# FLUIDIC_CTRL.net
KiCad netlist of a schematic drawn in Altium Designer
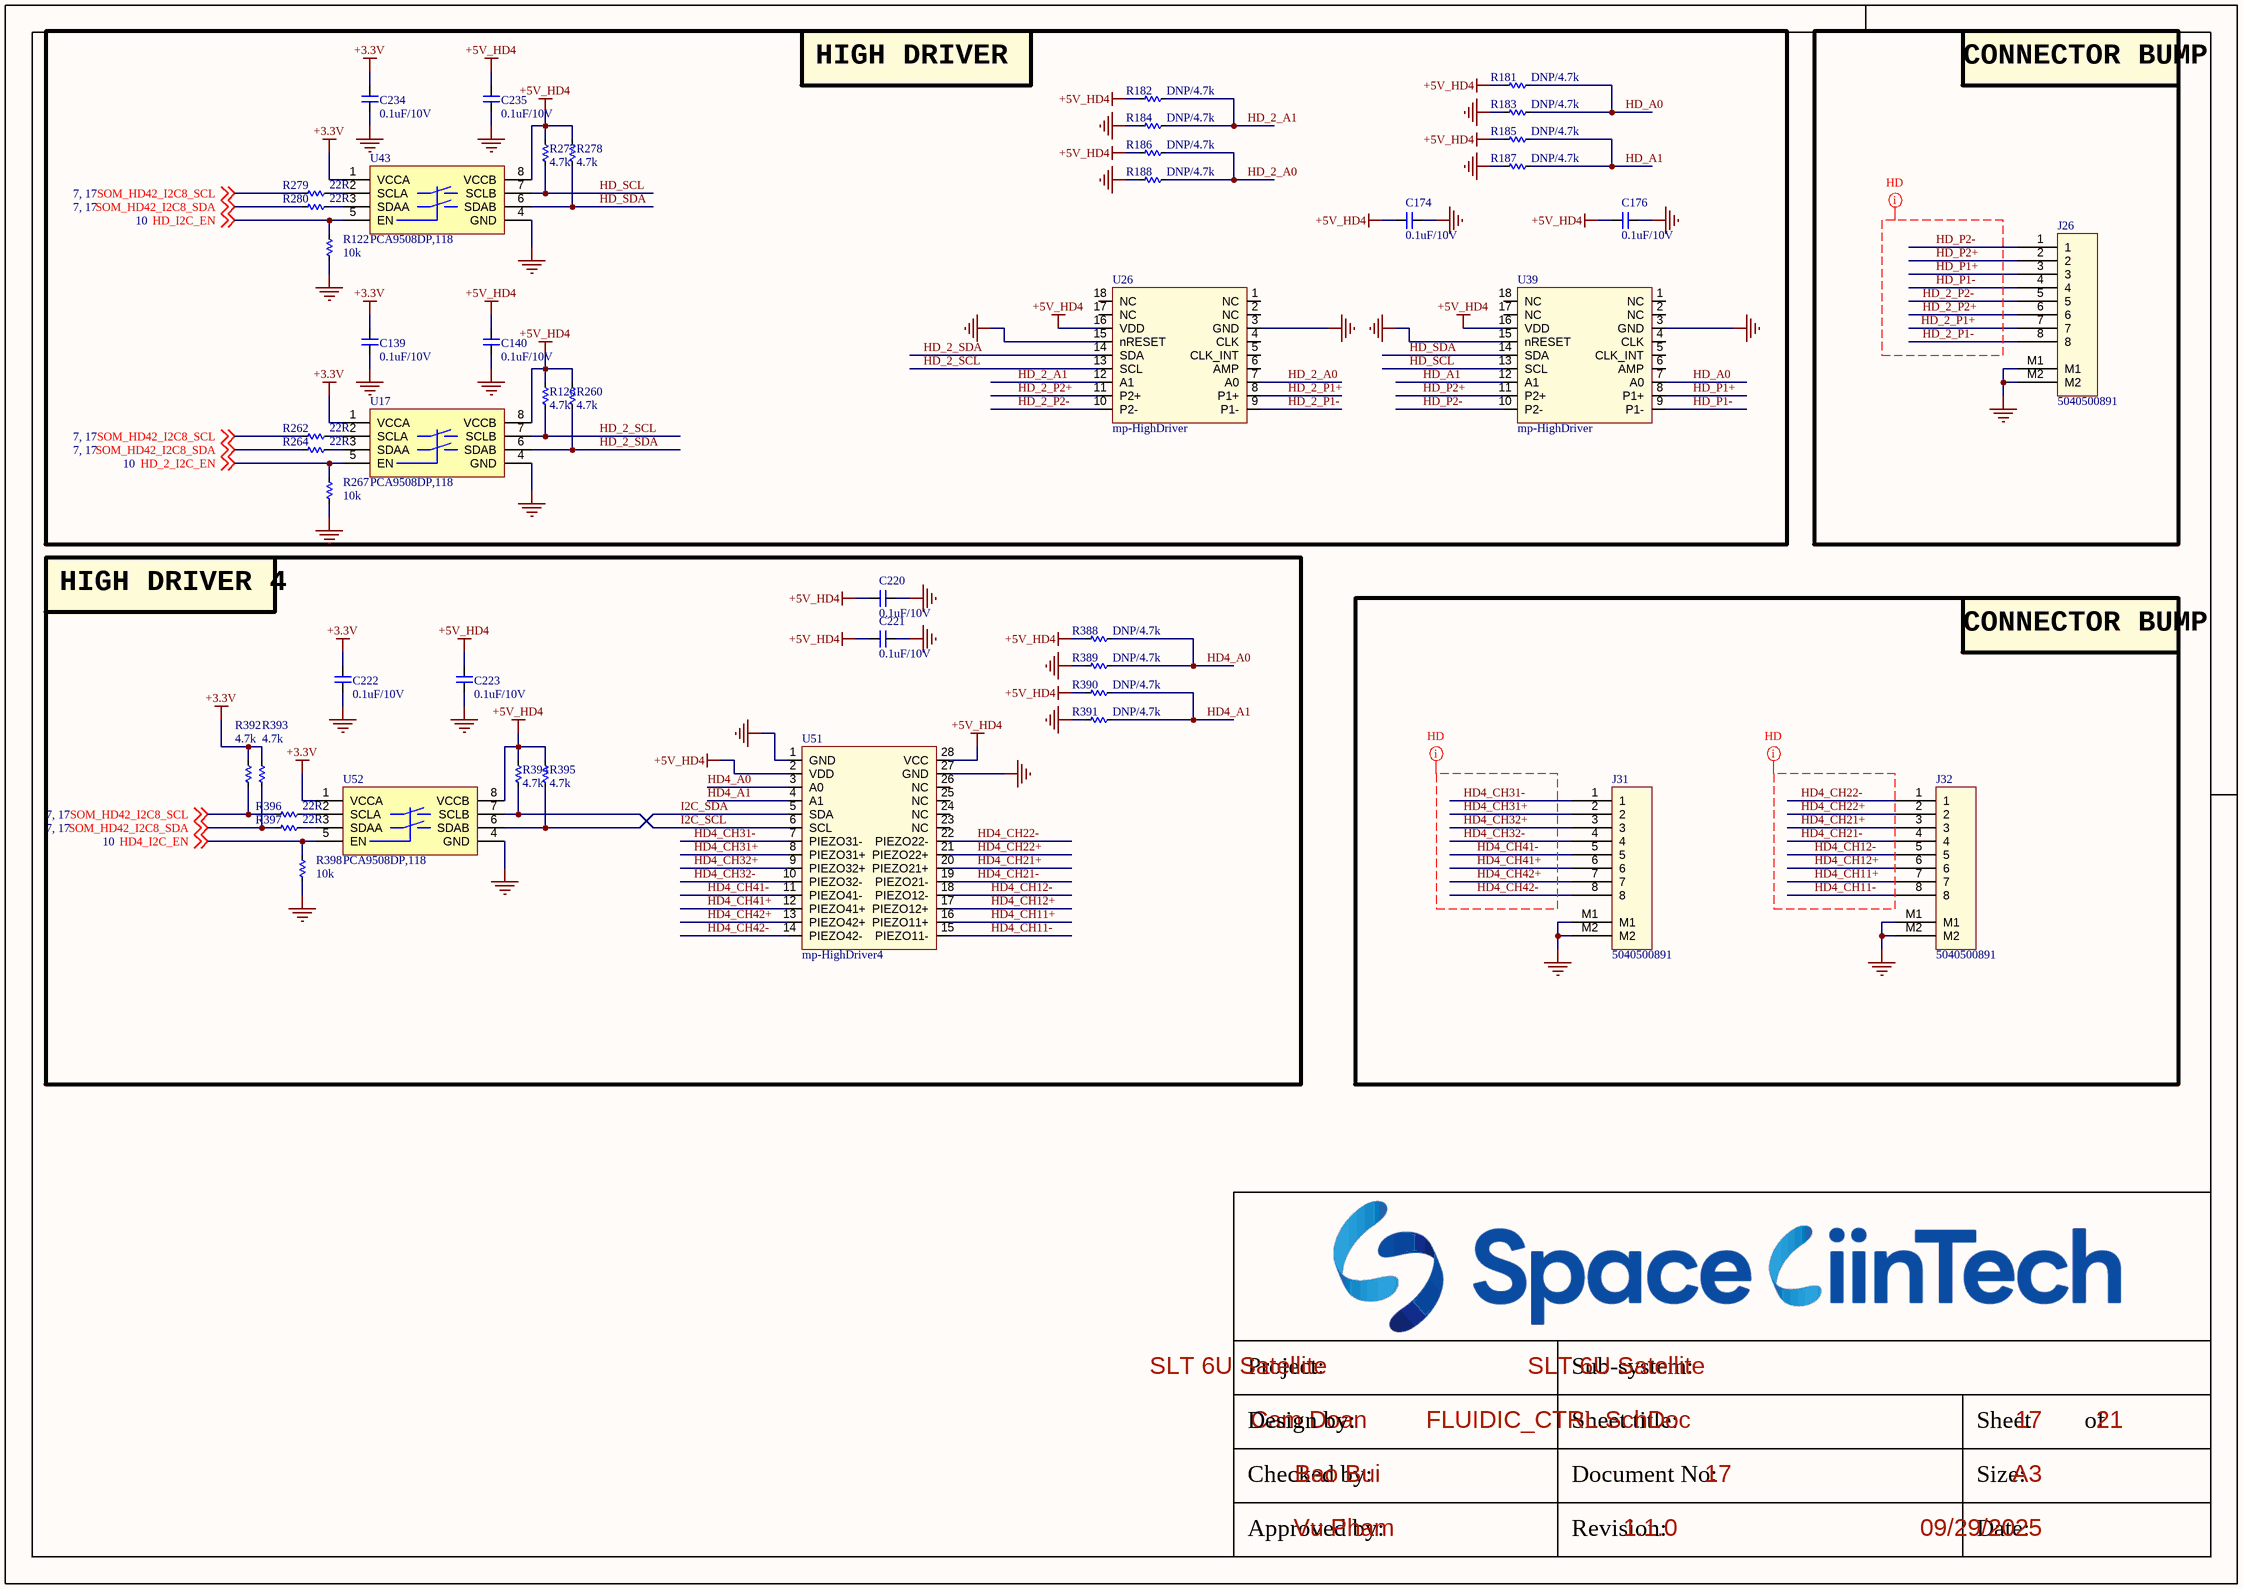
[diagram p0: FLUIDIC_CTRL.SchDoc]

(export (version "E")
  (design (tool "Eeschema 10.0.6"))
  (components
    (comp (ref "C139")
      (value "0.1uF/10V")
      (footprint "CAP_C_1005X60")
      (description "CAP CHIP")
      (libsource (lib "LABLIB") (part "_CAP_C_2"))
    )
    (comp (ref "C140")
      (value "0.1uF/10V")
      (footprint "CAP_C_1005X60")
      (description "CAP CHIP")
      (libsource (lib "LABLIB") (part "_CAP_C_2"))
    )
    (comp (ref "C174")
      (value "0.1uF/10V")
      (footprint "CAP_C_1005X60")
      (description "CAP CHIP")
      (libsource (lib "LABLIB") (part "_CAP_C_2"))
    )
    (comp (ref "C176")
      (value "0.1uF/10V")
      (footprint "CAP_C_1005X60")
      (description "CAP CHIP")
      (libsource (lib "LABLIB") (part "_CAP_C_2"))
    )
    (comp (ref "C220")
      (value "0.1uF/10V")
      (footprint "CAP_C_1005X60")
      (description "CAP CHIP")
      (libsource (lib "LABLIB") (part "_CAP_C_2"))
    )
    (comp (ref "C221")
      (value "0.1uF/10V")
      (footprint "CAP_C_1005X60")
      (description "CAP CHIP")
      (libsource (lib "LABLIB") (part "_CAP_C_2"))
    )
    (comp (ref "C222")
      (value "0.1uF/10V")
      (footprint "CAP_C_1005X60")
      (description "CAP CHIP")
      (libsource (lib "LABLIB") (part "_CAP_C_2"))
    )
    (comp (ref "C223")
      (value "0.1uF/10V")
      (footprint "CAP_C_1005X60")
      (description "CAP CHIP")
      (libsource (lib "LABLIB") (part "_CAP_C_2"))
    )
    (comp (ref "C234")
      (value "0.1uF/10V")
      (footprint "CAP_C_1005X60")
      (description "CAP CHIP")
      (libsource (lib "LABLIB") (part "_CAP_C_2"))
    )
    (comp (ref "C235")
      (value "0.1uF/10V")
      (footprint "CAP_C_1005X60")
      (description "CAP CHIP")
      (libsource (lib "LABLIB") (part "_CAP_C_2"))
    )
    (comp (ref "J26")
      (value "5040500891")
      (footprint "MOLEX_5040500891")
      (libsource (lib "LABLIB") (part "Header 8x1_2M"))
    )
    (comp (ref "J31")
      (value "5040500891")
      (footprint "MOLEX_5040500891")
      (libsource (lib "LABLIB") (part "Header 8x1_2M"))
    )
    (comp (ref "J32")
      (value "5040500891")
      (footprint "MOLEX_5040500891")
      (libsource (lib "LABLIB") (part "Header 8x1_2M"))
    )
    (comp (ref "R122")
      (value "10k")
      (footprint "RES_C_1005X40")
      (description "RES")
      (libsource (lib "LABLIB") (part "_RES_B_2"))
    )
    (comp (ref "R126")
      (value "4.7k")
      (footprint "RES_C_1005X40")
      (description "RES")
      (libsource (lib "LABLIB") (part "_RES_B_2"))
    )
    (comp (ref "R181")
      (value "DNP/4.7k")
      (footprint "RES_C_1005X40")
      (description "RES")
      (libsource (lib "LABLIB") (part "_RES_B_2"))
    )
    (comp (ref "R182")
      (value "DNP/4.7k")
      (footprint "RES_C_1005X40")
      (description "RES")
      (libsource (lib "LABLIB") (part "_RES_B_2"))
    )
    (comp (ref "R183")
      (value "DNP/4.7k")
      (footprint "RES_C_1005X40")
      (description "RES")
      (libsource (lib "LABLIB") (part "_RES_B_2"))
    )
    (comp (ref "R184")
      (value "DNP/4.7k")
      (footprint "RES_C_1005X40")
      (description "RES")
      (libsource (lib "LABLIB") (part "_RES_B_2"))
    )
    (comp (ref "R185")
      (value "DNP/4.7k")
      (footprint "RES_C_1005X40")
      (description "RES")
      (libsource (lib "LABLIB") (part "_RES_B_2"))
    )
    (comp (ref "R186")
      (value "DNP/4.7k")
      (footprint "RES_C_1005X40")
      (description "RES")
      (libsource (lib "LABLIB") (part "_RES_B_2"))
    )
    (comp (ref "R187")
      (value "DNP/4.7k")
      (footprint "RES_C_1005X40")
      (description "RES")
      (libsource (lib "LABLIB") (part "_RES_B_2"))
    )
    (comp (ref "R188")
      (value "DNP/4.7k")
      (footprint "RES_C_1005X40")
      (description "RES")
      (libsource (lib "LABLIB") (part "_RES_B_2"))
    )
    (comp (ref "R260")
      (value "4.7k")
      (footprint "RES_C_1005X40")
      (description "RES")
      (libsource (lib "LABLIB") (part "_RES_B_2"))
    )
    (comp (ref "R262")
      (value "22R")
      (footprint "RES_C_1005X40")
      (description "RES")
      (libsource (lib "LABLIB") (part "_RES_B_2"))
    )
    (comp (ref "R264")
      (value "22R")
      (footprint "RES_C_1005X40")
      (description "RES")
      (libsource (lib "LABLIB") (part "_RES_B_2"))
    )
    (comp (ref "R267")
      (value "10k")
      (footprint "RES_C_1005X40")
      (description "RES")
      (libsource (lib "LABLIB") (part "_RES_B_2"))
    )
    (comp (ref "R277")
      (value "4.7k")
      (footprint "RES_C_1005X40")
      (description "RES")
      (libsource (lib "LABLIB") (part "_RES_B_2"))
    )
    (comp (ref "R278")
      (value "4.7k")
      (footprint "RES_C_1005X40")
      (description "RES")
      (libsource (lib "LABLIB") (part "_RES_B_2"))
    )
    (comp (ref "R279")
      (value "22R")
      (footprint "RES_C_1005X40")
      (description "RES")
      (libsource (lib "LABLIB") (part "_RES_B_2"))
    )
    (comp (ref "R280")
      (value "22R")
      (footprint "RES_C_1005X40")
      (description "RES")
      (libsource (lib "LABLIB") (part "_RES_B_2"))
    )
    (comp (ref "R388")
      (value "DNP/4.7k")
      (footprint "RES_C_1005X40")
      (description "RES")
      (libsource (lib "LABLIB") (part "_RES_B_2"))
    )
    (comp (ref "R389")
      (value "DNP/4.7k")
      (footprint "RES_C_1005X40")
      (description "RES")
      (libsource (lib "LABLIB") (part "_RES_B_2"))
    )
    (comp (ref "R390")
      (value "DNP/4.7k")
      (footprint "RES_C_1005X40")
      (description "RES")
      (libsource (lib "LABLIB") (part "_RES_B_2"))
    )
    (comp (ref "R391")
      (value "DNP/4.7k")
      (footprint "RES_C_1005X40")
      (description "RES")
      (libsource (lib "LABLIB") (part "_RES_B_2"))
    )
    (comp (ref "R392")
      (value "4.7k")
      (footprint "RES_C_1005X40")
      (description "RES")
      (libsource (lib "LABLIB") (part "_RES_B_2"))
    )
    (comp (ref "R393")
      (value "4.7k")
      (footprint "RES_C_1005X40")
      (description "RES")
      (libsource (lib "LABLIB") (part "_RES_B_2"))
    )
    (comp (ref "R394")
      (value "4.7k")
      (footprint "RES_C_1005X40")
      (description "RES")
      (libsource (lib "LABLIB") (part "_RES_B_2"))
    )
    (comp (ref "R395")
      (value "4.7k")
      (footprint "RES_C_1005X40")
      (description "RES")
      (libsource (lib "LABLIB") (part "_RES_B_2"))
    )
    (comp (ref "R396")
      (value "22R")
      (footprint "RES_C_1005X40")
      (description "RES")
      (libsource (lib "LABLIB") (part "_RES_B_2"))
    )
    (comp (ref "R397")
      (value "22R")
      (footprint "RES_C_1005X40")
      (description "RES")
      (libsource (lib "LABLIB") (part "_RES_B_2"))
    )
    (comp (ref "R398")
      (value "10k")
      (footprint "RES_C_1005X40")
      (description "RES")
      (libsource (lib "LABLIB") (part "_RES_B_2"))
    )
    (comp (ref "U17")
      (value "PCA9508DP,118")
      (footprint "TSOP8")
      (libsource (lib "EXP_HW_V3") (part "PCA9508DP,118"))
    )
    (comp (ref "U26")
      (value "mp-HighDriver")
      (footprint "MP_HIGHDRIVER")
      (libsource (lib "new_component") (part "mp-HighDriver"))
    )
    (comp (ref "U39")
      (value "mp-HighDriver")
      (footprint "MP_HIGHDRIVER")
      (libsource (lib "new_component") (part "mp-HighDriver"))
    )
    (comp (ref "U43")
      (value "PCA9508DP,118")
      (footprint "TSOP8")
      (libsource (lib "EXP_HW_V3") (part "PCA9508DP,118"))
    )
    (comp (ref "U51")
      (value "mp-HighDriver4")
      (footprint "MP_HIGHDRIVER4")
      (libsource (lib "new_component") (part "mp_HighDriver4"))
    )
    (comp (ref "U52")
      (value "PCA9508DP,118")
      (footprint "TSOP8")
      (libsource (lib "EXP_HW_V3") (part "PCA9508DP,118"))
    )
  )
  (nets
    (net (code "1") (name "+3.3V") (class "Default")
      (node (ref "C139") (pin "2") (pinfunction "2_2") (pintype "passive"))
      (node (ref "C222") (pin "2") (pinfunction "2_2") (pintype "passive"))
      (node (ref "C234") (pin "2") (pinfunction "2_2") (pintype "passive"))
      (node (ref "R392") (pin "1") (pinfunction "1_1") (pintype "passive"))
      (node (ref "R393") (pin "1") (pinfunction "1_1") (pintype "passive"))
      (node (ref "U17") (pin "1") (pinfunction "VCCA_1") (pintype "passive"))
      (node (ref "U43") (pin "1") (pinfunction "VCCA_1") (pintype "passive"))
      (node (ref "U52") (pin "1") (pinfunction "VCCA_1") (pintype "passive"))
    )
    (net (code "2") (name "+5V_HD4") (class "Default")
      (node (ref "C140") (pin "2") (pinfunction "2_2") (pintype "passive"))
      (node (ref "C174") (pin "2") (pinfunction "2_2") (pintype "passive"))
      (node (ref "C176") (pin "2") (pinfunction "2_2") (pintype "passive"))
      (node (ref "C220") (pin "2") (pinfunction "2_2") (pintype "passive"))
      (node (ref "C221") (pin "2") (pinfunction "2_2") (pintype "passive"))
      (node (ref "C223") (pin "2") (pinfunction "2_2") (pintype "passive"))
      (node (ref "C235") (pin "2") (pinfunction "2_2") (pintype "passive"))
      (node (ref "R126") (pin "1") (pinfunction "1_1") (pintype "passive"))
      (node (ref "R181") (pin "1") (pinfunction "1_1") (pintype "passive"))
      (node (ref "R182") (pin "1") (pinfunction "1_1") (pintype "passive"))
      (node (ref "R185") (pin "1") (pinfunction "1_1") (pintype "passive"))
      (node (ref "R186") (pin "1") (pinfunction "1_1") (pintype "passive"))
      (node (ref "R260") (pin "1") (pinfunction "1_1") (pintype "passive"))
      (node (ref "R277") (pin "1") (pinfunction "1_1") (pintype "passive"))
      (node (ref "R278") (pin "1") (pinfunction "1_1") (pintype "passive"))
      (node (ref "R388") (pin "1") (pinfunction "1_1") (pintype "passive"))
      (node (ref "R390") (pin "1") (pinfunction "1_1") (pintype "passive"))
      (node (ref "R394") (pin "1") (pinfunction "1_1") (pintype "passive"))
      (node (ref "R395") (pin "1") (pinfunction "1_1") (pintype "passive"))
      (node (ref "U17") (pin "8") (pinfunction "VCCB_8") (pintype "passive"))
      (node (ref "U26") (pin "16") (pinfunction "VDD_16") (pintype "power_in"))
      (node (ref "U39") (pin "16") (pinfunction "VDD_16") (pintype "power_in"))
      (node (ref "U43") (pin "8") (pinfunction "VCCB_8") (pintype "passive"))
      (node (ref "U51") (pin "2") (pinfunction "VDD_2") (pintype "power_in"))
      (node (ref "U51") (pin "28") (pinfunction "VCC_28") (pintype "power_in"))
      (node (ref "U52") (pin "8") (pinfunction "VCCB_8") (pintype "passive"))
    )
    (net (code "3") (name "/HD4_A0") (class "Default")
      (node (ref "R388") (pin "2") (pinfunction "2_2") (pintype "passive"))
      (node (ref "R389") (pin "2") (pinfunction "2_2") (pintype "passive"))
      (node (ref "U51") (pin "3") (pinfunction "A0_3") (pintype "passive"))
    )
    (net (code "4") (name "/HD4_A1") (class "Default")
      (node (ref "R390") (pin "2") (pinfunction "2_2") (pintype "passive"))
      (node (ref "R391") (pin "2") (pinfunction "2_2") (pintype "passive"))
      (node (ref "U51") (pin "4") (pinfunction "A1_4") (pintype "passive"))
    )
    (net (code "5") (name "/HD4_CH11+") (class "Default")
      (node (ref "J32") (pin "7") (pinfunction "7_7") (pintype "passive"))
      (node (ref "U51") (pin "16") (pinfunction "PIEZO11+_16") (pintype "passive"))
    )
    (net (code "6") (name "/HD4_CH11-") (class "Default")
      (node (ref "J32") (pin "8") (pinfunction "8_8") (pintype "passive"))
      (node (ref "U51") (pin "15") (pinfunction "PIEZO11-_15") (pintype "passive"))
    )
    (net (code "7") (name "/HD4_CH12+") (class "Default")
      (node (ref "J32") (pin "6") (pinfunction "6_6") (pintype "passive"))
      (node (ref "U51") (pin "17") (pinfunction "PIEZO12+_17") (pintype "passive"))
    )
    (net (code "8") (name "/HD4_CH12-") (class "Default")
      (node (ref "J32") (pin "5") (pinfunction "5_5") (pintype "passive"))
      (node (ref "U51") (pin "18") (pinfunction "PIEZO12-_18") (pintype "passive"))
    )
    (net (code "9") (name "/HD4_CH21+") (class "Default")
      (node (ref "J32") (pin "3") (pinfunction "3_3") (pintype "passive"))
      (node (ref "U51") (pin "20") (pinfunction "PIEZO21+_20") (pintype "passive"))
    )
    (net (code "10") (name "/HD4_CH21-") (class "Default")
      (node (ref "J32") (pin "4") (pinfunction "4_4") (pintype "passive"))
      (node (ref "U51") (pin "19") (pinfunction "PIEZO21-_19") (pintype "passive"))
    )
    (net (code "11") (name "/HD4_CH22+") (class "Default")
      (node (ref "J32") (pin "2") (pinfunction "2_2") (pintype "passive"))
      (node (ref "U51") (pin "21") (pinfunction "PIEZO22+_21") (pintype "passive"))
    )
    (net (code "12") (name "/HD4_CH22-") (class "Default")
      (node (ref "J32") (pin "1") (pinfunction "1_1") (pintype "passive"))
      (node (ref "U51") (pin "22") (pinfunction "PIEZO22-_22") (pintype "passive"))
    )
    (net (code "13") (name "/HD4_CH31+") (class "Default")
      (node (ref "J31") (pin "2") (pinfunction "2_2") (pintype "passive"))
      (node (ref "U51") (pin "8") (pinfunction "PIEZO31+_8") (pintype "passive"))
    )
    (net (code "14") (name "/HD4_CH31-") (class "Default")
      (node (ref "J31") (pin "1") (pinfunction "1_1") (pintype "passive"))
      (node (ref "U51") (pin "7") (pinfunction "PIEZO31-_7") (pintype "passive"))
    )
    (net (code "15") (name "/HD4_CH32+") (class "Default")
      (node (ref "J31") (pin "3") (pinfunction "3_3") (pintype "passive"))
      (node (ref "U51") (pin "9") (pinfunction "PIEZO32+_9") (pintype "passive"))
    )
    (net (code "16") (name "/HD4_CH32-") (class "Default")
      (node (ref "J31") (pin "4") (pinfunction "4_4") (pintype "passive"))
      (node (ref "U51") (pin "10") (pinfunction "PIEZO32-_10") (pintype "passive"))
    )
    (net (code "17") (name "/HD4_CH41+") (class "Default")
      (node (ref "J31") (pin "6") (pinfunction "6_6") (pintype "passive"))
      (node (ref "U51") (pin "12") (pinfunction "PIEZO41+_12") (pintype "passive"))
    )
    (net (code "18") (name "/HD4_CH41-") (class "Default")
      (node (ref "J31") (pin "5") (pinfunction "5_5") (pintype "passive"))
      (node (ref "U51") (pin "11") (pinfunction "PIEZO41-_11") (pintype "passive"))
    )
    (net (code "19") (name "/HD4_CH42+") (class "Default")
      (node (ref "J31") (pin "7") (pinfunction "7_7") (pintype "passive"))
      (node (ref "U51") (pin "13") (pinfunction "PIEZO42+_13") (pintype "passive"))
    )
    (net (code "20") (name "/HD4_CH42-") (class "Default")
      (node (ref "J31") (pin "8") (pinfunction "8_8") (pintype "passive"))
      (node (ref "U51") (pin "14") (pinfunction "PIEZO42-_14") (pintype "passive"))
    )
    (net (code "21") (name "/HD_2_A0") (class "Default")
      (node (ref "R186") (pin "2") (pinfunction "2_2") (pintype "passive"))
      (node (ref "R188") (pin "2") (pinfunction "2_2") (pintype "passive"))
      (node (ref "U26") (pin "7") (pinfunction "A0_7") (pintype "passive"))
    )
    (net (code "22") (name "/HD_2_A1") (class "Default")
      (node (ref "R182") (pin "2") (pinfunction "2_2") (pintype "passive"))
      (node (ref "R184") (pin "2") (pinfunction "2_2") (pintype "passive"))
      (node (ref "U26") (pin "12") (pinfunction "A1_12") (pintype "passive"))
    )
    (net (code "23") (name "/HD_2_P1+") (class "Default")
      (node (ref "J26") (pin "7") (pinfunction "7_7") (pintype "passive"))
      (node (ref "U26") (pin "8") (pinfunction "P1+_8") (pintype "passive"))
    )
    (net (code "24") (name "/HD_2_P1-") (class "Default")
      (node (ref "J26") (pin "8") (pinfunction "8_8") (pintype "passive"))
      (node (ref "U26") (pin "9") (pinfunction "P1-_9") (pintype "passive"))
    )
    (net (code "25") (name "/HD_2_P2+") (class "Default")
      (node (ref "J26") (pin "6") (pinfunction "6_6") (pintype "passive"))
      (node (ref "U26") (pin "11") (pinfunction "P2+_11") (pintype "passive"))
    )
    (net (code "26") (name "/HD_2_P2-") (class "Default")
      (node (ref "J26") (pin "5") (pinfunction "5_5") (pintype "passive"))
      (node (ref "U26") (pin "10") (pinfunction "P2-_10") (pintype "passive"))
    )
    (net (code "27") (name "/HD_2_SCL") (class "Default")
      (node (ref "R126") (pin "2") (pinfunction "2_2") (pintype "passive"))
      (node (ref "U17") (pin "7") (pinfunction "SCLB_7") (pintype "passive"))
      (node (ref "U26") (pin "13") (pinfunction "SCL_13") (pintype "passive"))
    )
    (net (code "28") (name "/HD_2_SDA") (class "Default")
      (node (ref "R260") (pin "2") (pinfunction "2_2") (pintype "passive"))
      (node (ref "U17") (pin "6") (pinfunction "SDAB_6") (pintype "passive"))
      (node (ref "U26") (pin "14") (pinfunction "SDA_14") (pintype "passive"))
    )
    (net (code "29") (name "/HD_A0") (class "Default")
      (node (ref "R181") (pin "2") (pinfunction "2_2") (pintype "passive"))
      (node (ref "R183") (pin "2") (pinfunction "2_2") (pintype "passive"))
      (node (ref "U39") (pin "7") (pinfunction "A0_7") (pintype "passive"))
    )
    (net (code "30") (name "/HD_A1") (class "Default")
      (node (ref "R185") (pin "2") (pinfunction "2_2") (pintype "passive"))
      (node (ref "R187") (pin "2") (pinfunction "2_2") (pintype "passive"))
      (node (ref "U39") (pin "12") (pinfunction "A1_12") (pintype "passive"))
    )
    (net (code "31") (name "/HD_P1+") (class "Default")
      (node (ref "J26") (pin "3") (pinfunction "3_3") (pintype "passive"))
      (node (ref "U39") (pin "8") (pinfunction "P1+_8") (pintype "passive"))
    )
    (net (code "32") (name "/HD_P1-") (class "Default")
      (node (ref "J26") (pin "4") (pinfunction "4_4") (pintype "passive"))
      (node (ref "U39") (pin "9") (pinfunction "P1-_9") (pintype "passive"))
    )
    (net (code "33") (name "/HD_P2+") (class "Default")
      (node (ref "J26") (pin "2") (pinfunction "2_2") (pintype "passive"))
      (node (ref "U39") (pin "11") (pinfunction "P2+_11") (pintype "passive"))
    )
    (net (code "34") (name "/HD_P2-") (class "Default")
      (node (ref "J26") (pin "1") (pinfunction "1_1") (pintype "passive"))
      (node (ref "U39") (pin "10") (pinfunction "P2-_10") (pintype "passive"))
    )
    (net (code "35") (name "/HD_SCL") (class "Default")
      (node (ref "R277") (pin "2") (pinfunction "2_2") (pintype "passive"))
      (node (ref "U39") (pin "13") (pinfunction "SCL_13") (pintype "passive"))
      (node (ref "U43") (pin "7") (pinfunction "SCLB_7") (pintype "passive"))
    )
    (net (code "36") (name "/HD_SDA") (class "Default")
      (node (ref "R278") (pin "2") (pinfunction "2_2") (pintype "passive"))
      (node (ref "U39") (pin "14") (pinfunction "SDA_14") (pintype "passive"))
      (node (ref "U43") (pin "6") (pinfunction "SDAB_6") (pintype "passive"))
    )
    (net (code "37") (name "/I2C_SCL") (class "Default")
      (node (ref "R394") (pin "2") (pinfunction "2_2") (pintype "passive"))
      (node (ref "U51") (pin "6") (pinfunction "SCL_6") (pintype "passive"))
      (node (ref "U52") (pin "7") (pinfunction "SCLB_7") (pintype "passive"))
    )
    (net (code "38") (name "/I2C_SDA") (class "Default")
      (node (ref "R395") (pin "2") (pinfunction "2_2") (pintype "passive"))
      (node (ref "U51") (pin "5") (pinfunction "SDA_5") (pintype "passive"))
      (node (ref "U52") (pin "6") (pinfunction "SDAB_6") (pintype "passive"))
    )
    (net (code "39") (name "GND") (class "Default")
      (node (ref "C139") (pin "1") (pinfunction "1_1") (pintype "passive"))
      (node (ref "C140") (pin "1") (pinfunction "1_1") (pintype "passive"))
      (node (ref "C174") (pin "1") (pinfunction "1_1") (pintype "passive"))
      (node (ref "C176") (pin "1") (pinfunction "1_1") (pintype "passive"))
      (node (ref "C220") (pin "1") (pinfunction "1_1") (pintype "passive"))
      (node (ref "C221") (pin "1") (pinfunction "1_1") (pintype "passive"))
      (node (ref "C222") (pin "1") (pinfunction "1_1") (pintype "passive"))
      (node (ref "C223") (pin "1") (pinfunction "1_1") (pintype "passive"))
      (node (ref "C234") (pin "1") (pinfunction "1_1") (pintype "passive"))
      (node (ref "C235") (pin "1") (pinfunction "1_1") (pintype "passive"))
      (node (ref "J26") (pin "M1") (pinfunction "M1_M1") (pintype "passive"))
      (node (ref "J26") (pin "M2") (pinfunction "M2_M2") (pintype "passive"))
      (node (ref "J31") (pin "M1") (pinfunction "M1_M1") (pintype "passive"))
      (node (ref "J31") (pin "M2") (pinfunction "M2_M2") (pintype "passive"))
      (node (ref "J32") (pin "M1") (pinfunction "M1_M1") (pintype "passive"))
      (node (ref "J32") (pin "M2") (pinfunction "M2_M2") (pintype "passive"))
      (node (ref "R122") (pin "2") (pinfunction "2_2") (pintype "passive"))
      (node (ref "R183") (pin "1") (pinfunction "1_1") (pintype "passive"))
      (node (ref "R184") (pin "1") (pinfunction "1_1") (pintype "passive"))
      (node (ref "R187") (pin "1") (pinfunction "1_1") (pintype "passive"))
      (node (ref "R188") (pin "1") (pinfunction "1_1") (pintype "passive"))
      (node (ref "R267") (pin "2") (pinfunction "2_2") (pintype "passive"))
      (node (ref "R389") (pin "1") (pinfunction "1_1") (pintype "passive"))
      (node (ref "R391") (pin "1") (pinfunction "1_1") (pintype "passive"))
      (node (ref "R398") (pin "2") (pinfunction "2_2") (pintype "passive"))
      (node (ref "U17") (pin "4") (pinfunction "GND_4") (pintype "passive"))
      (node (ref "U26") (pin "15") (pinfunction "nRESET_15") (pintype "passive"))
      (node (ref "U26") (pin "3") (pinfunction "GND_3") (pintype "power_in"))
      (node (ref "U39") (pin "15") (pinfunction "nRESET_15") (pintype "passive"))
      (node (ref "U39") (pin "3") (pinfunction "GND_3") (pintype "power_in"))
      (node (ref "U43") (pin "4") (pinfunction "GND_4") (pintype "passive"))
      (node (ref "U51") (pin "1") (pinfunction "GND_1") (pintype "power_in"))
      (node (ref "U51") (pin "27") (pinfunction "GND_27") (pintype "power_in"))
      (node (ref "U52") (pin "4") (pinfunction "GND_4") (pintype "passive"))
    )
    (net (code "40") (name "HD4_I2C_EN") (class "Default")
      (node (ref "R398") (pin "1") (pinfunction "1_1") (pintype "passive"))
      (node (ref "U52") (pin "5") (pinfunction "EN_5") (pintype "passive"))
    )
    (net (code "41") (name "HD_2_I2C_EN") (class "Default")
      (node (ref "R267") (pin "1") (pinfunction "1_1") (pintype "passive"))
      (node (ref "U17") (pin "5") (pinfunction "EN_5") (pintype "passive"))
    )
    (net (code "42") (name "HD_I2C_EN") (class "Default")
      (node (ref "R122") (pin "1") (pinfunction "1_1") (pintype "passive"))
      (node (ref "U43") (pin "5") (pinfunction "EN_5") (pintype "passive"))
    )
    (net (code "43") (name "Net-(U17-SCLA)") (class "Default")
      (node (ref "R262") (pin "1") (pinfunction "1_1") (pintype "passive"))
      (node (ref "U17") (pin "2") (pinfunction "SCLA_2") (pintype "passive"))
    )
    (net (code "44") (name "Net-(U17-SDAA)") (class "Default")
      (node (ref "R264") (pin "1") (pinfunction "1_1") (pintype "passive"))
      (node (ref "U17") (pin "3") (pinfunction "SDAA_3") (pintype "passive"))
    )
    (net (code "45") (name "Net-(U43-SCLA)") (class "Default")
      (node (ref "R279") (pin "1") (pinfunction "1_1") (pintype "passive"))
      (node (ref "U43") (pin "2") (pinfunction "SCLA_2") (pintype "passive"))
    )
    (net (code "46") (name "Net-(U43-SDAA)") (class "Default")
      (node (ref "R280") (pin "1") (pinfunction "1_1") (pintype "passive"))
      (node (ref "U43") (pin "3") (pinfunction "SDAA_3") (pintype "passive"))
    )
    (net (code "47") (name "Net-(U52-SCLA)") (class "Default")
      (node (ref "R396") (pin "1") (pinfunction "1_1") (pintype "passive"))
      (node (ref "U52") (pin "2") (pinfunction "SCLA_2") (pintype "passive"))
    )
    (net (code "48") (name "Net-(U52-SDAA)") (class "Default")
      (node (ref "R397") (pin "1") (pinfunction "1_1") (pintype "passive"))
      (node (ref "U52") (pin "3") (pinfunction "SDAA_3") (pintype "passive"))
    )
    (net (code "49") (name "SOM_HD42_I2C8_SCL") (class "Default")
      (node (ref "R262") (pin "2") (pinfunction "2_2") (pintype "passive"))
      (node (ref "R279") (pin "2") (pinfunction "2_2") (pintype "passive"))
      (node (ref "R392") (pin "2") (pinfunction "2_2") (pintype "passive"))
      (node (ref "R396") (pin "2") (pinfunction "2_2") (pintype "passive"))
    )
    (net (code "50") (name "SOM_HD42_I2C8_SDA") (class "Default")
      (node (ref "R264") (pin "2") (pinfunction "2_2") (pintype "passive"))
      (node (ref "R280") (pin "2") (pinfunction "2_2") (pintype "passive"))
      (node (ref "R393") (pin "2") (pinfunction "2_2") (pintype "passive"))
      (node (ref "R397") (pin "2") (pinfunction "2_2") (pintype "passive"))
    )
    (net (code "51") (name "unconnected-(U26-AMP-Pad6)") (class "Default")
      (node (ref "U26") (pin "6") (pinfunction "AMP_6") (pintype "passive"))
    )
    (net (code "52") (name "unconnected-(U26-CLK-Pad4)") (class "Default")
      (node (ref "U26") (pin "4") (pinfunction "CLK_4") (pintype "passive"))
    )
    (net (code "53") (name "unconnected-(U26-CLK_INT-Pad5)") (class "Default")
      (node (ref "U26") (pin "5") (pinfunction "CLK_INT_5") (pintype "passive"))
    )
    (net (code "54") (name "unconnected-(U26-NC-Pad1)") (class "Default")
      (node (ref "U26") (pin "1") (pinfunction "NC_1") (pintype "passive"))
    )
    (net (code "55") (name "unconnected-(U26-NC-Pad2)") (class "Default")
      (node (ref "U26") (pin "2") (pinfunction "NC_2") (pintype "passive"))
    )
    (net (code "56") (name "unconnected-(U26-NC-Pad17)") (class "Default")
      (node (ref "U26") (pin "17") (pinfunction "NC_17") (pintype "passive"))
    )
    (net (code "57") (name "unconnected-(U26-NC-Pad18)") (class "Default")
      (node (ref "U26") (pin "18") (pinfunction "NC_18") (pintype "passive"))
    )
    (net (code "58") (name "unconnected-(U39-AMP-Pad6)") (class "Default")
      (node (ref "U39") (pin "6") (pinfunction "AMP_6") (pintype "passive"))
    )
    (net (code "59") (name "unconnected-(U39-CLK-Pad4)") (class "Default")
      (node (ref "U39") (pin "4") (pinfunction "CLK_4") (pintype "passive"))
    )
    (net (code "60") (name "unconnected-(U39-CLK_INT-Pad5)") (class "Default")
      (node (ref "U39") (pin "5") (pinfunction "CLK_INT_5") (pintype "passive"))
    )
    (net (code "61") (name "unconnected-(U39-NC-Pad1)") (class "Default")
      (node (ref "U39") (pin "1") (pinfunction "NC_1") (pintype "passive"))
    )
    (net (code "62") (name "unconnected-(U39-NC-Pad2)") (class "Default")
      (node (ref "U39") (pin "2") (pinfunction "NC_2") (pintype "passive"))
    )
    (net (code "63") (name "unconnected-(U39-NC-Pad17)") (class "Default")
      (node (ref "U39") (pin "17") (pinfunction "NC_17") (pintype "passive"))
    )
    (net (code "64") (name "unconnected-(U39-NC-Pad18)") (class "Default")
      (node (ref "U39") (pin "18") (pinfunction "NC_18") (pintype "passive"))
    )
    (net (code "65") (name "unconnected-(U51-NC-Pad23)") (class "Default")
      (node (ref "U51") (pin "23") (pinfunction "NC_23") (pintype "passive"))
    )
    (net (code "66") (name "unconnected-(U51-NC-Pad24)") (class "Default")
      (node (ref "U51") (pin "24") (pinfunction "NC_24") (pintype "passive"))
    )
    (net (code "67") (name "unconnected-(U51-NC-Pad25)") (class "Default")
      (node (ref "U51") (pin "25") (pinfunction "NC_25") (pintype "passive"))
    )
    (net (code "68") (name "unconnected-(U51-NC-Pad26)") (class "Default")
      (node (ref "U51") (pin "26") (pinfunction "NC_26") (pintype "passive"))
    )
  )
)
